# AC-DC_Convertor_Rev1.net
KiCad netlist of a schematic drawn in EAGLE
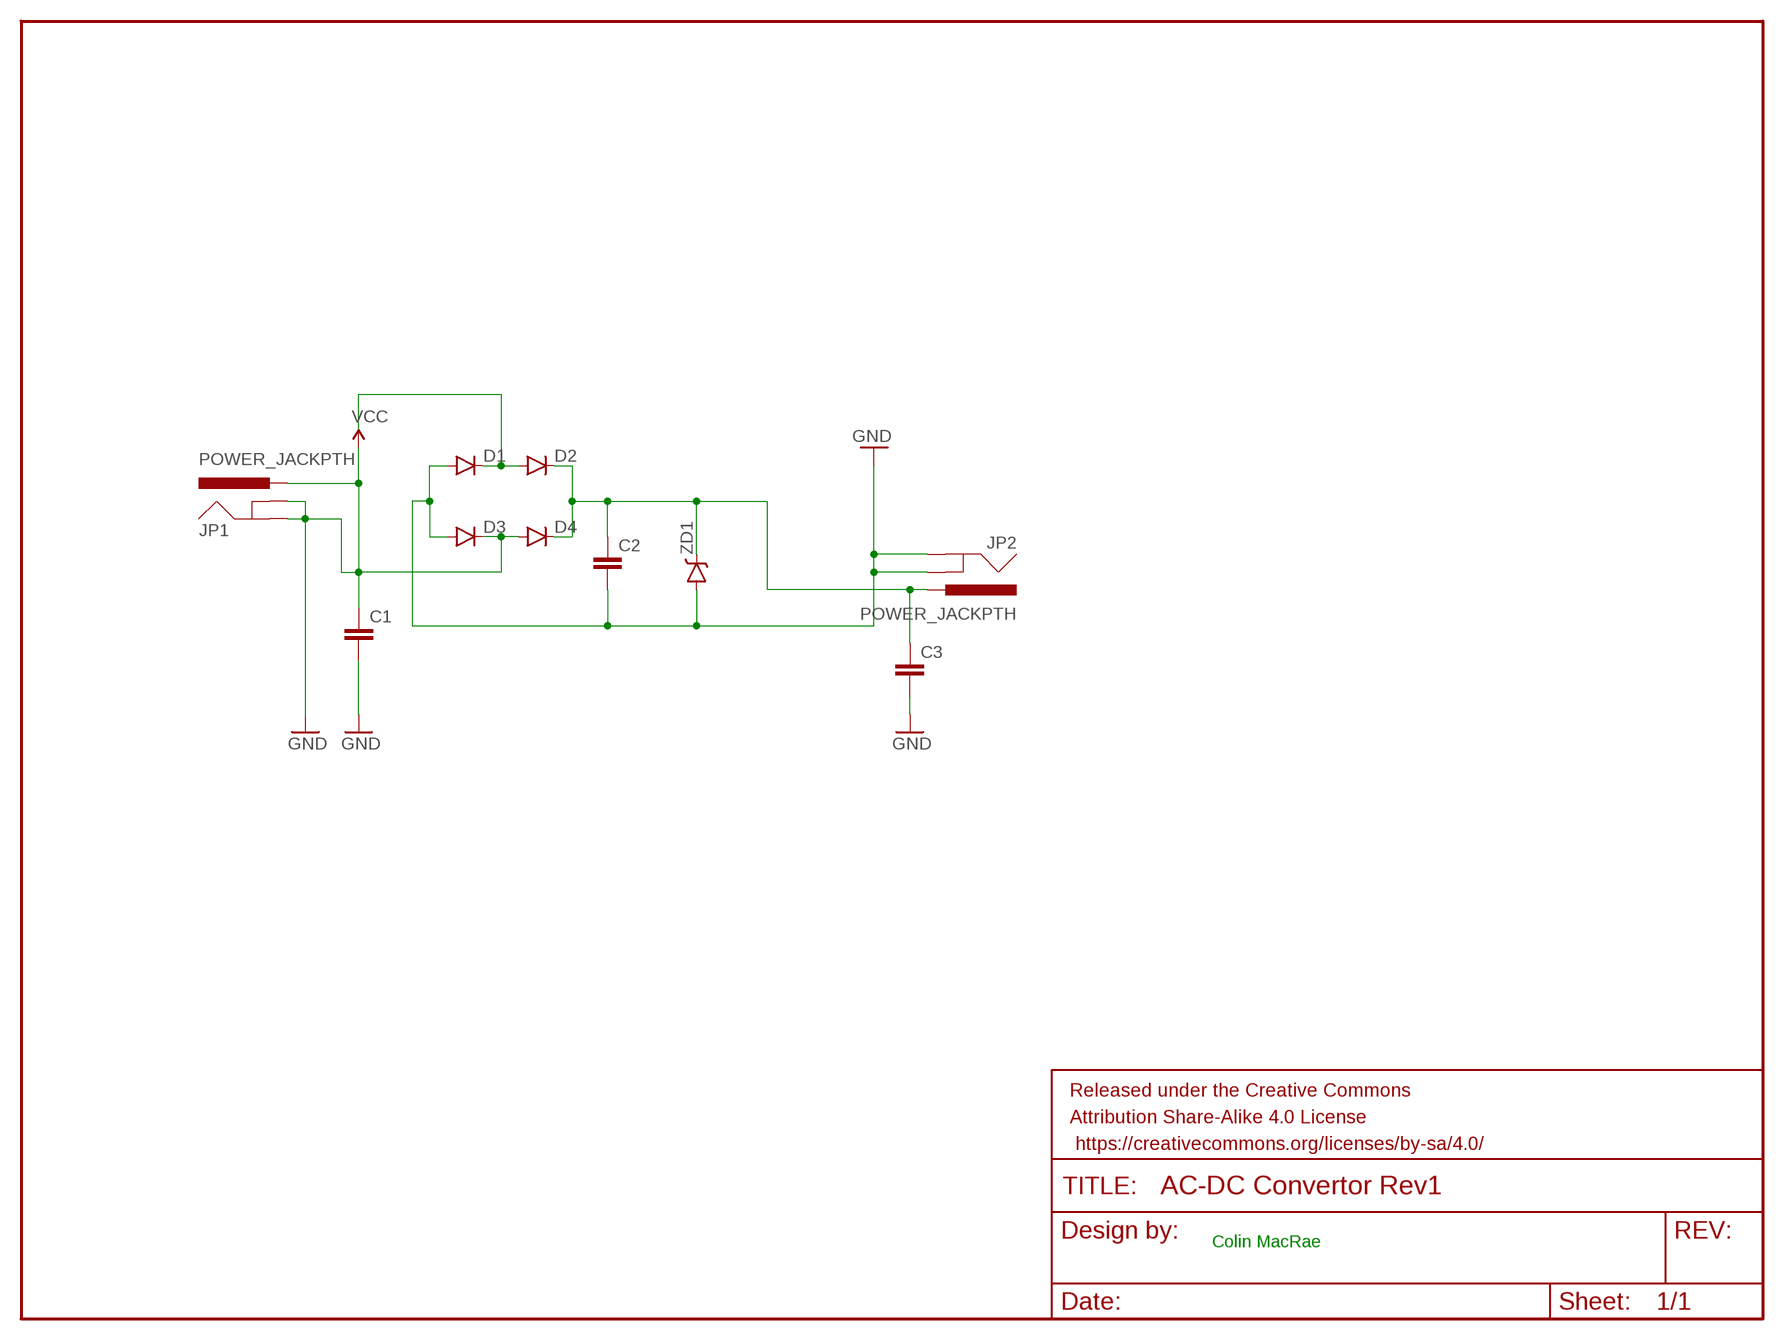
[diagram p0: schematic, sheet 1]

(export (version "E")
  (design (tool "Eeschema 10.0.6"))
  (components
    (comp (ref "C1")
      (value "CAPEZ")
      (footprint "eagle-import:CAP-PTH-SMALLEZ")
      (libsource (lib "eagle-import") (part "CAPEZ"))
    )
    (comp (ref "C2")
      (value "CAPEZ")
      (footprint "eagle-import:CAP-PTH-SMALLEZ")
      (libsource (lib "eagle-import") (part "CAPEZ"))
    )
    (comp (ref "C3")
      (value "CAPEZ")
      (footprint "eagle-import:CAP-PTH-SMALLEZ")
      (libsource (lib "eagle-import") (part "CAPEZ"))
    )
    (comp (ref "D1")
      (value "DIODEKIT2")
      (footprint "eagle-import:DIODE-1N4001-KIT")
      (libsource (lib "eagle-import") (part "DIODEKIT2"))
    )
    (comp (ref "D2")
      (value "DIODEKIT2")
      (footprint "eagle-import:DIODE-1N4001-KIT")
      (libsource (lib "eagle-import") (part "DIODEKIT2"))
    )
    (comp (ref "D3")
      (value "DIODEKIT2")
      (footprint "eagle-import:DIODE-1N4001-KIT")
      (libsource (lib "eagle-import") (part "DIODEKIT2"))
    )
    (comp (ref "D4")
      (value "DIODEKIT2")
      (footprint "eagle-import:DIODE-1N4001-KIT")
      (libsource (lib "eagle-import") (part "DIODEKIT2"))
    )
    (comp (ref "FRAME1")
      (value "FRAME-LETTER")
      (footprint "eagle-import:CREATIVE_COMMONS")
      (libsource (lib "eagle-import") (part "FRAME-LETTER"))
    )
    (comp (ref "JP1")
      (value "POWER_JACKPTH")
      (footprint "eagle-import:POWER_JACK_PTH")
      (libsource (lib "eagle-import") (part "POWER_JACKPTH"))
    )
    (comp (ref "JP2")
      (value "POWER_JACKPTH")
      (footprint "eagle-import:POWER_JACK_PTH")
      (libsource (lib "eagle-import") (part "POWER_JACKPTH"))
    )
    (comp (ref "ZD1")
      (value "V-REFERENCESMD")
      (footprint "eagle-import:SOT23-3")
      (libsource (lib "eagle-import") (part "V-REFERENCESMD"))
    )
  )
  (nets
    (net (code "1") (name "GND") (class "Default")
      (node (ref "C1") (pin "1") (pinfunction "1_1") (pintype "passive"))
      (node (ref "C1") (pin "2") (pinfunction "2_2") (pintype "passive"))
      (node (ref "C2") (pin "2") (pinfunction "2_2") (pintype "passive"))
      (node (ref "C3") (pin "2") (pinfunction "2_2") (pintype "passive"))
      (node (ref "D1") (pin "A") (pinfunction "A_A") (pintype "passive"))
      (node (ref "D3") (pin "A") (pinfunction "A_A") (pintype "passive"))
      (node (ref "D3") (pin "C") (pinfunction "C_C") (pintype "passive"))
      (node (ref "D4") (pin "A") (pinfunction "A_A") (pintype "passive"))
      (node (ref "JP1") (pin "GND") (pinfunction "GND_GND") (pintype "bidirectional"))
      (node (ref "JP1") (pin "GNDBREAK") (pinfunction "GNDBREAK_GNDBREAK") (pintype "bidirectional"))
      (node (ref "JP1") (pin "PWR") (pinfunction "PWR_PWR") (pintype "bidirectional"))
      (node (ref "JP2") (pin "GND") (pinfunction "GND_GND") (pintype "bidirectional"))
      (node (ref "JP2") (pin "GNDBREAK") (pinfunction "GNDBREAK_GNDBREAK") (pintype "bidirectional"))
      (node (ref "ZD1") (pin "2") (pinfunction "A_2") (pintype "passive"))
    )
    (net (code "2") (name "Net-(D1-PadC)") (class "Default")
      (node (ref "D1") (pin "C") (pinfunction "C_C") (pintype "passive"))
      (node (ref "D2") (pin "A") (pinfunction "A_A") (pintype "passive"))
    )
    (net (code "3") (name "Net-(ZD1-C)") (class "Default")
      (node (ref "C2") (pin "1") (pinfunction "1_1") (pintype "passive"))
      (node (ref "C3") (pin "1") (pinfunction "1_1") (pintype "passive"))
      (node (ref "D2") (pin "C") (pinfunction "C_C") (pintype "passive"))
      (node (ref "D4") (pin "C") (pinfunction "C_C") (pintype "passive"))
      (node (ref "JP2") (pin "PWR") (pinfunction "PWR_PWR") (pintype "bidirectional"))
      (node (ref "ZD1") (pin "1") (pinfunction "C_1") (pintype "passive"))
    )
  )
)
